# Other.net
KiCad netlist of a schematic drawn in Altium Designer
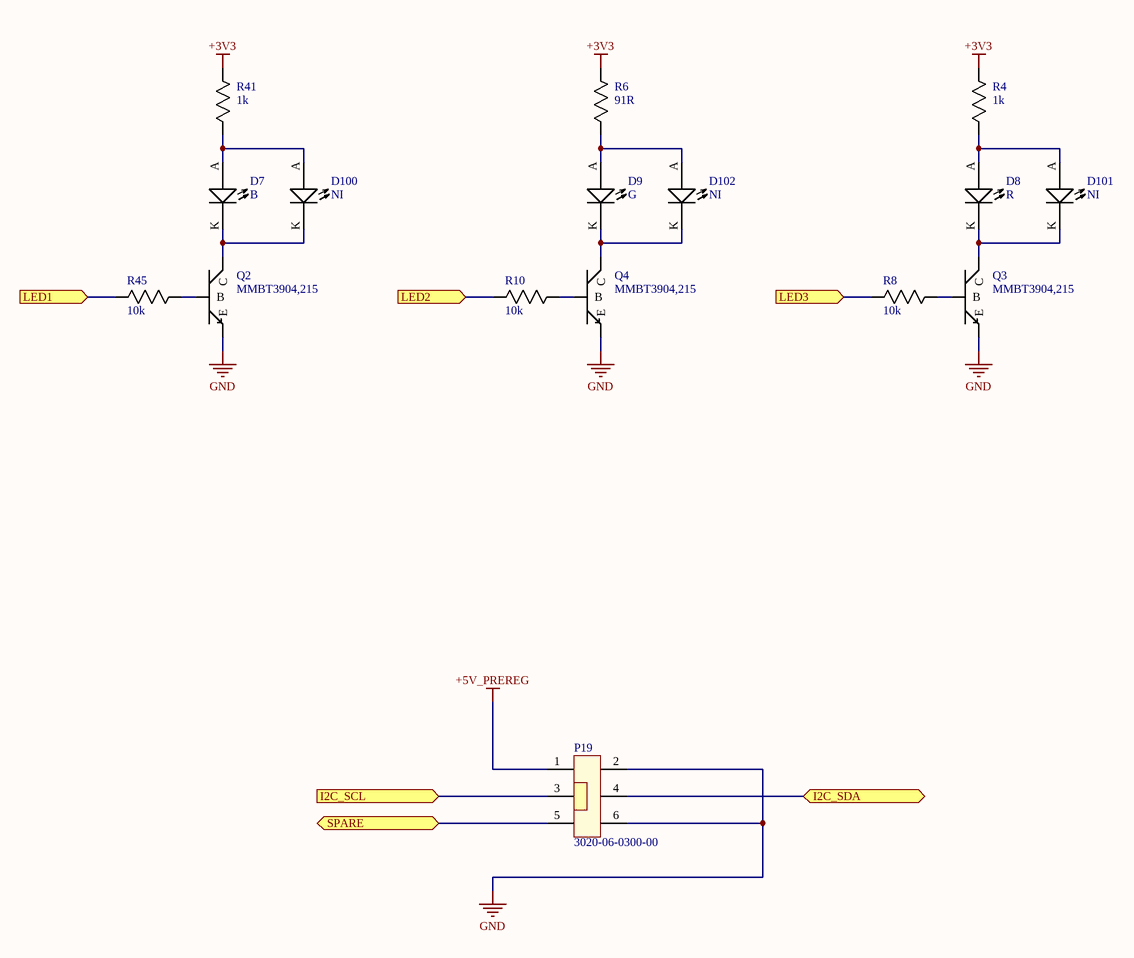
[diagram p0: Other.SchDoc]

(export (version "E")
  (design (tool "Eeschema 10.0.6"))
  (components
    (comp (ref "D7")
      (value "Diode_LED")
      (footprint "0805_LED")
      (description "LED")
      (fields (field (name "MFG") "Wurth") (field (name "TYPE") "B"))
      (libsource (lib "INTER_2014") (part "Diode_LED"))
    )
    (comp (ref "D8")
      (value "Diode_LED")
      (footprint "0805_LED")
      (description "LED")
      (fields (field (name "MFG") "Osram") (field (name "TYPE") "R"))
      (libsource (lib "INTER_2014") (part "Diode_LED"))
    )
    (comp (ref "D9")
      (value "Diode_LED")
      (footprint "0805_LED")
      (description "LED")
      (fields (field (name "MFG") "Osram") (field (name "TYPE") "G"))
      (libsource (lib "INTER_2014") (part "Diode_LED"))
    )
    (comp (ref "D100")
      (value "Diode_LED")
      (footprint "0805_LED")
      (description "LED")
      (fields (field (name "NI") "NI"))
      (libsource (lib "INTER_2014") (part "Diode_LED"))
    )
    (comp (ref "D101")
      (value "Diode_LED")
      (footprint "0805_LED")
      (description "LED")
      (fields (field (name "NI") "NI"))
      (libsource (lib "INTER_2014") (part "Diode_LED"))
    )
    (comp (ref "D102")
      (value "Diode_LED")
      (footprint "0805_LED")
      (description "LED")
      (fields (field (name "NI") "NI"))
      (libsource (lib "INTER_2014") (part "Diode_LED"))
    )
    (comp (ref "P19")
      (value "CON6_3020-06-0300-00")
      (footprint "CONN6_100mils_pol_SMD")
      (description "6-pins")
      (fields (field (name "MFG") "Harwin") (field (name "MFG_PN") "3020-06-0300-00"))
      (libsource (lib "INTER_2014") (part "CON6_3020-06-0300-00"))
    )
    (comp (ref "Q2")
      (value "BJT_N_GDS")
      (footprint "SOT23_GDS")
      (description "BJT NPN")
      (fields (field (name "MFG") "NXP") (field (name "MFG_PN") "MMBT3904,215"))
      (libsource (lib "INTER_2014") (part "BJT_N_GDS"))
    )
    (comp (ref "Q3")
      (value "BJT_N_GDS")
      (footprint "SOT23_GDS")
      (description "BJT NPN")
      (fields (field (name "MFG") "NXP") (field (name "MFG_PN") "MMBT3904,215"))
      (libsource (lib "INTER_2014") (part "BJT_N_GDS"))
    )
    (comp (ref "Q4")
      (value "BJT_N_GDS")
      (footprint "SOT23_GDS")
      (description "BJT NPN")
      (fields (field (name "MFG") "NXP") (field (name "MFG_PN") "MMBT3904,215"))
      (libsource (lib "INTER_2014") (part "BJT_N_GDS"))
    )
    (comp (ref "R4")
      (value "1k")
      (footprint "0603")
      (description "Resistor")
      (libsource (lib "INTER_2014") (part "Resistor"))
    )
    (comp (ref "R6")
      (value "91R")
      (footprint "0603")
      (description "Resistor")
      (libsource (lib "INTER_2014") (part "Resistor"))
    )
    (comp (ref "R8")
      (value "10k")
      (footprint "0603")
      (description "Resistor")
      (libsource (lib "INTER_2014") (part "Resistor"))
    )
    (comp (ref "R10")
      (value "10k")
      (footprint "0603")
      (description "Resistor")
      (libsource (lib "INTER_2014") (part "Resistor"))
    )
    (comp (ref "R41")
      (value "1k")
      (footprint "0603")
      (description "Resistor")
      (libsource (lib "INTER_2014") (part "Resistor"))
    )
    (comp (ref "R45")
      (value "10k")
      (footprint "0603")
      (description "Resistor")
      (libsource (lib "INTER_2014") (part "Resistor"))
    )
  )
  (nets
    (net (code "1") (name "+3V3") (class "Default")
      (node (ref "R4") (pin "2") (pintype "passive"))
      (node (ref "R41") (pin "2") (pintype "passive"))
      (node (ref "R6") (pin "2") (pintype "passive"))
    )
    (net (code "2") (name "+5V_PREREG") (class "Default") (node (ref "P19") (pin "1") (pintype "passive")))
    (net (code "3") (name "/I2C_SCL") (class "Default") (node (ref "P19") (pin "3") (pintype "passive")))
    (net (code "4") (name "/I2C_SDA") (class "Default") (node (ref "P19") (pin "4") (pintype "passive")))
    (net (code "5") (name "/LED1") (class "Default") (node (ref "R45") (pin "1") (pintype "passive")))
    (net (code "6") (name "/LED2") (class "Default") (node (ref "R10") (pin "1") (pintype "passive")))
    (net (code "7") (name "/LED3") (class "Default") (node (ref "R8") (pin "1") (pintype "passive")))
    (net (code "8") (name "/SPARE") (class "Default") (node (ref "P19") (pin "5") (pintype "passive")))
    (net (code "9") (name "GND") (class "Default")
      (node (ref "P19") (pin "2") (pintype "passive"))
      (node (ref "P19") (pin "6") (pintype "passive"))
      (node (ref "Q2") (pin "S") (pinfunction "E_S") (pintype "passive"))
      (node (ref "Q3") (pin "S") (pinfunction "E_S") (pintype "passive"))
      (node (ref "Q4") (pin "S") (pinfunction "E_S") (pintype "passive"))
    )
    (net (code "10") (name "Net-(D100-PadA)") (class "Default")
      (node (ref "D100") (pin "A") (pintype "passive"))
      (node (ref "D7") (pin "A") (pintype "passive"))
      (node (ref "R41") (pin "1") (pintype "passive"))
    )
    (net (code "11") (name "Net-(D101-PadA)") (class "Default")
      (node (ref "D101") (pin "A") (pintype "passive"))
      (node (ref "D8") (pin "A") (pintype "passive"))
      (node (ref "R4") (pin "1") (pintype "passive"))
    )
    (net (code "12") (name "Net-(D102-PadA)") (class "Default")
      (node (ref "D102") (pin "A") (pintype "passive"))
      (node (ref "D9") (pin "A") (pintype "passive"))
      (node (ref "R6") (pin "1") (pintype "passive"))
    )
    (net (code "13") (name "Net-(Q2-B)") (class "Default")
      (node (ref "Q2") (pin "G") (pinfunction "B_G") (pintype "passive"))
      (node (ref "R45") (pin "2") (pintype "passive"))
    )
    (net (code "14") (name "Net-(Q2-C)") (class "Default")
      (node (ref "D100") (pin "K") (pintype "passive"))
      (node (ref "D7") (pin "K") (pintype "passive"))
      (node (ref "Q2") (pin "D") (pinfunction "C_D") (pintype "passive"))
    )
    (net (code "15") (name "Net-(Q3-B)") (class "Default")
      (node (ref "Q3") (pin "G") (pinfunction "B_G") (pintype "passive"))
      (node (ref "R8") (pin "2") (pintype "passive"))
    )
    (net (code "16") (name "Net-(Q3-C)") (class "Default")
      (node (ref "D101") (pin "K") (pintype "passive"))
      (node (ref "D8") (pin "K") (pintype "passive"))
      (node (ref "Q3") (pin "D") (pinfunction "C_D") (pintype "passive"))
    )
    (net (code "17") (name "Net-(Q4-B)") (class "Default")
      (node (ref "Q4") (pin "G") (pinfunction "B_G") (pintype "passive"))
      (node (ref "R10") (pin "2") (pintype "passive"))
    )
    (net (code "18") (name "Net-(Q4-C)") (class "Default")
      (node (ref "D102") (pin "K") (pintype "passive"))
      (node (ref "D9") (pin "K") (pintype "passive"))
      (node (ref "Q4") (pin "D") (pinfunction "C_D") (pintype "passive"))
    )
  )
)
